# riser-1u-can.net
KiCad netlist of a schematic drawn in EAGLE
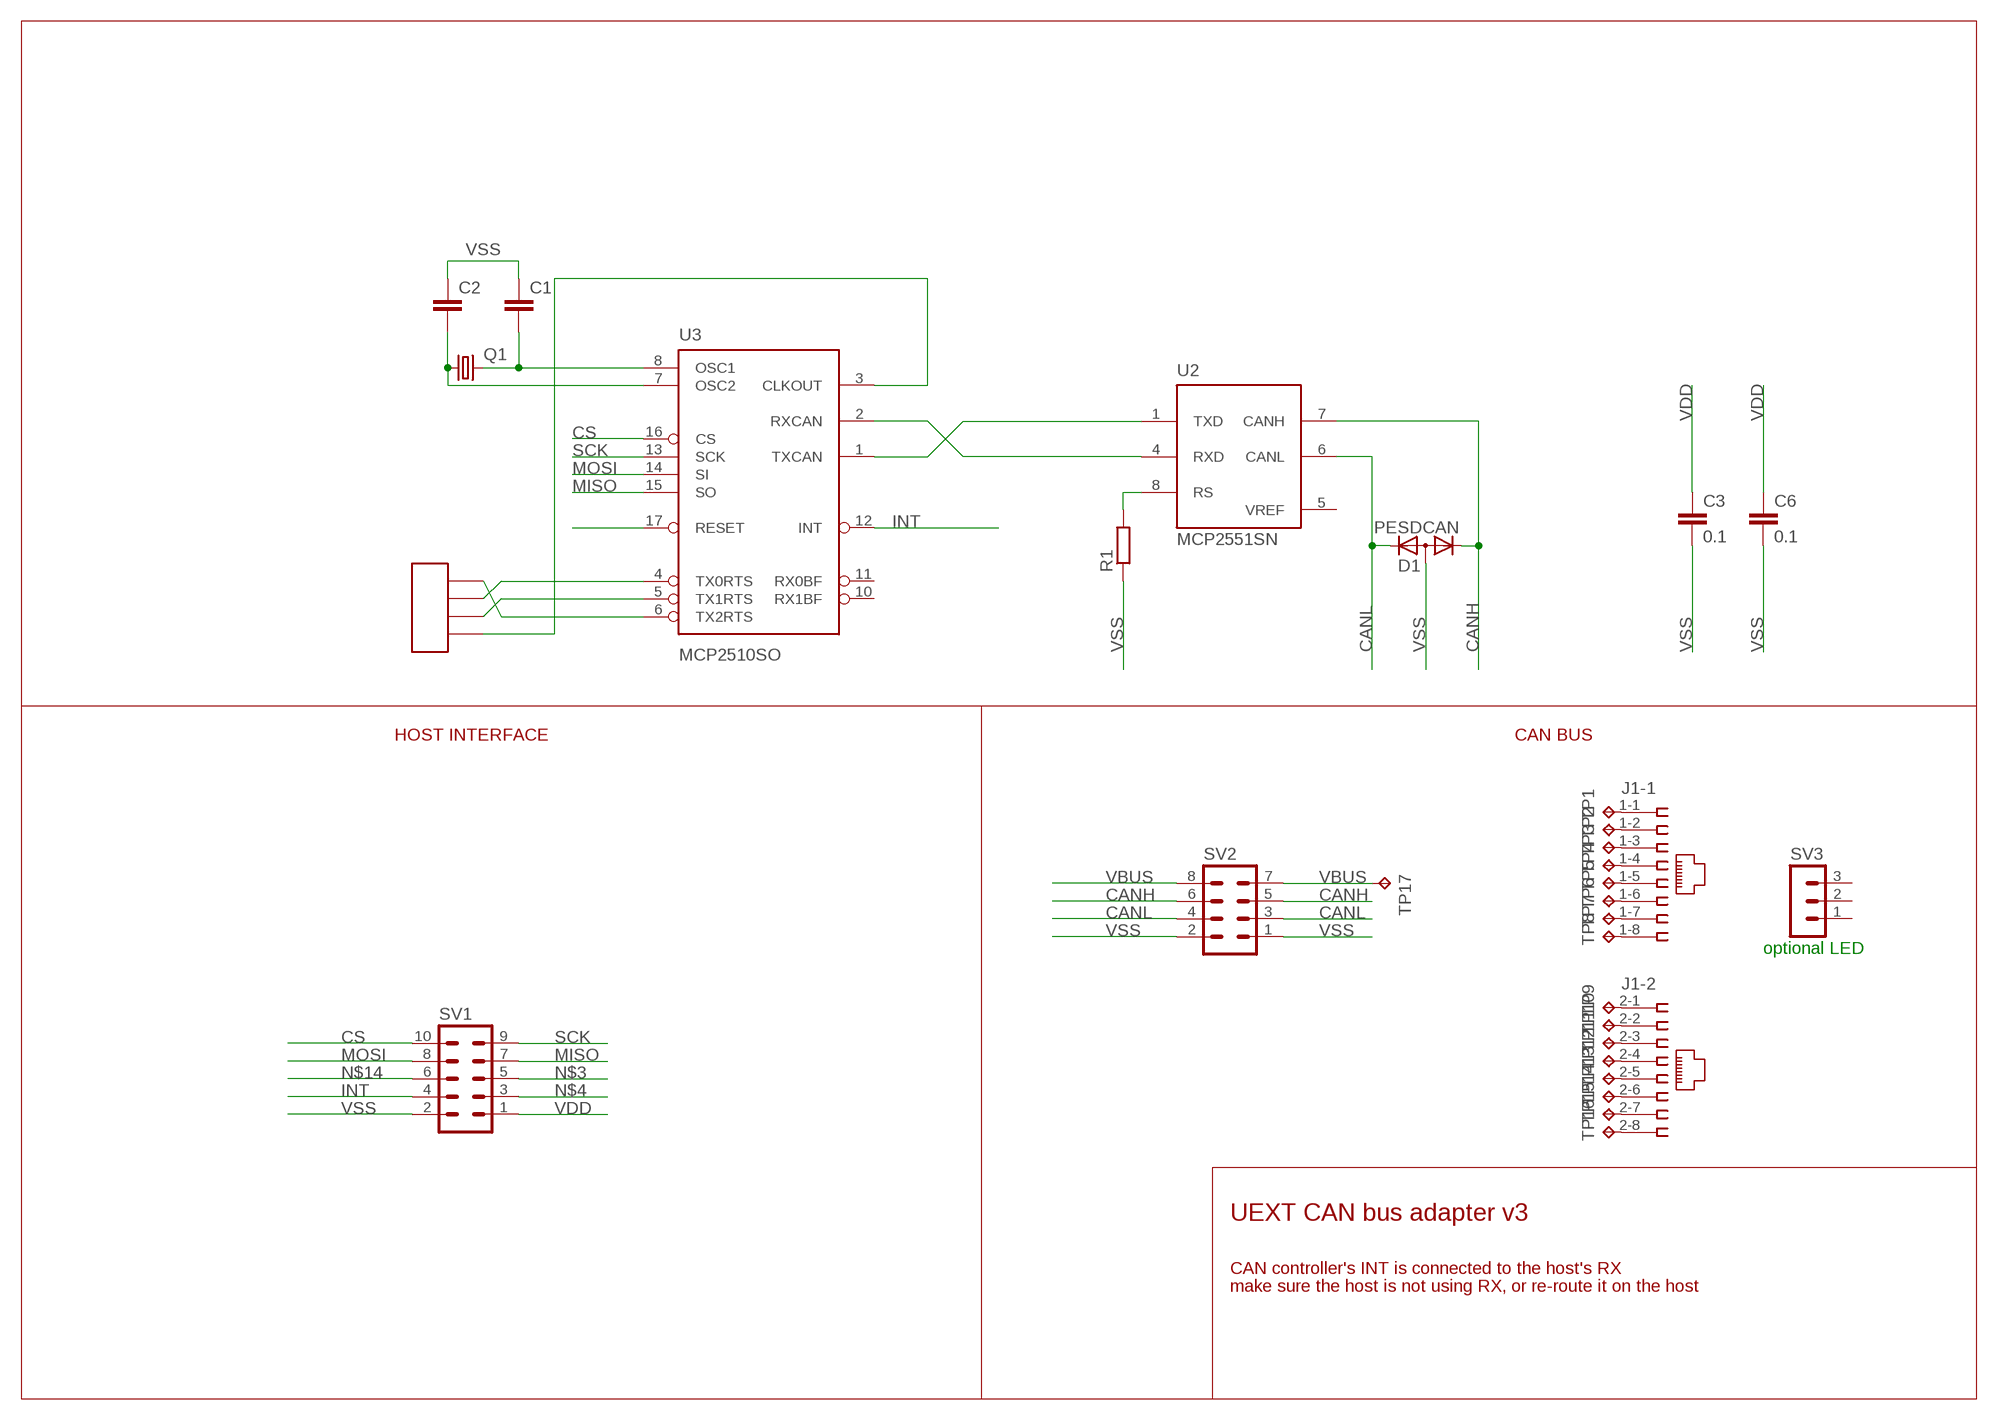
[diagram p0: schematic, sheet 1]

(export (version "E")
  (design (tool "Eeschema 10.0.6"))
  (components
    (comp (ref "C1")
      (value "C-EUC0805")
      (footprint "eagle-import:C0805")
      (libsource (lib "eagle-import") (part "C-EUC0805"))
    )
    (comp (ref "C2")
      (value "C-EUC0805")
      (footprint "eagle-import:C0805")
      (libsource (lib "eagle-import") (part "C-EUC0805"))
    )
    (comp (ref "C3")
      (value "0.1")
      (footprint "eagle-import:C0805")
      (libsource (lib "eagle-import") (part "C-EUC0805"))
    )
    (comp (ref "C6")
      (value "0.1")
      (footprint "eagle-import:C1206")
      (libsource (lib "eagle-import") (part "C-EUC1206"))
    )
    (comp (ref "D1")
      (value "PESDCAN")
      (footprint "eagle-import:SOT23")
      (libsource (lib "eagle-import") (part "DIODE-2CA|ACSOT23"))
    )
    (comp (ref "J1")
      (value "557560-1")
      (footprint "eagle-import:557560-1")
      (libsource (lib "eagle-import") (part "557560-1"))
    )
    (comp (ref "Q1")
      (value "CRYSTALHC49S")
      (footprint "eagle-import:HC49_S")
      (libsource (lib "eagle-import") (part "CRYSTALHC49S"))
    )
    (comp (ref "R1")
      (value "R-EU_R0603")
      (footprint "eagle-import:R0603")
      (libsource (lib "eagle-import") (part "R-EU_R0603"))
    )
    (comp (ref "SV1")
      (value "MA05-2")
      (footprint "eagle-import:MA05-2")
      (libsource (lib "eagle-import") (part "MA05-2"))
    )
    (comp (ref "SV2")
      (value "MA04-2")
      (footprint "eagle-import:MA04-2")
      (libsource (lib "eagle-import") (part "MA04-2"))
    )
    (comp (ref "SV3")
      (value "MA03-1")
      (footprint "eagle-import:MA03-1")
      (libsource (lib "eagle-import") (part "MA03-1"))
    )
    (comp (ref "TP1")
      (value "TPB1,27")
      (footprint "eagle-import:B1,27")
      (libsource (lib "eagle-import") (part "TPB1,27"))
    )
    (comp (ref "TP2")
      (value "TPB1,27")
      (footprint "eagle-import:B1,27")
      (libsource (lib "eagle-import") (part "TPB1,27"))
    )
    (comp (ref "TP3")
      (value "TPB1,27")
      (footprint "eagle-import:B1,27")
      (libsource (lib "eagle-import") (part "TPB1,27"))
    )
    (comp (ref "TP4")
      (value "TPB1,27")
      (footprint "eagle-import:B1,27")
      (libsource (lib "eagle-import") (part "TPB1,27"))
    )
    (comp (ref "TP5")
      (value "TPB1,27")
      (footprint "eagle-import:B1,27")
      (libsource (lib "eagle-import") (part "TPB1,27"))
    )
    (comp (ref "TP6")
      (value "TPB1,27")
      (footprint "eagle-import:B1,27")
      (libsource (lib "eagle-import") (part "TPB1,27"))
    )
    (comp (ref "TP7")
      (value "TPB1,27")
      (footprint "eagle-import:B1,27")
      (libsource (lib "eagle-import") (part "TPB1,27"))
    )
    (comp (ref "TP8")
      (value "TPB1,27")
      (footprint "eagle-import:B1,27")
      (libsource (lib "eagle-import") (part "TPB1,27"))
    )
    (comp (ref "TP9")
      (value "TPB1,27")
      (footprint "eagle-import:B1,27")
      (libsource (lib "eagle-import") (part "TPB1,27"))
    )
    (comp (ref "TP10")
      (value "TPB1,27")
      (footprint "eagle-import:B1,27")
      (libsource (lib "eagle-import") (part "TPB1,27"))
    )
    (comp (ref "TP11")
      (value "TPB1,27")
      (footprint "eagle-import:B1,27")
      (libsource (lib "eagle-import") (part "TPB1,27"))
    )
    (comp (ref "TP12")
      (value "TPB1,27")
      (footprint "eagle-import:B1,27")
      (libsource (lib "eagle-import") (part "TPB1,27"))
    )
    (comp (ref "TP13")
      (value "TPB1,27")
      (footprint "eagle-import:B1,27")
      (libsource (lib "eagle-import") (part "TPB1,27"))
    )
    (comp (ref "TP14")
      (value "TPB1,27")
      (footprint "eagle-import:B1,27")
      (libsource (lib "eagle-import") (part "TPB1,27"))
    )
    (comp (ref "TP15")
      (value "TPB1,27")
      (footprint "eagle-import:B1,27")
      (libsource (lib "eagle-import") (part "TPB1,27"))
    )
    (comp (ref "TP16")
      (value "TPB1,27")
      (footprint "eagle-import:B1,27")
      (libsource (lib "eagle-import") (part "TPB1,27"))
    )
    (comp (ref "TP17")
      (value "TPB1,27")
      (footprint "eagle-import:B1,27")
      (libsource (lib "eagle-import") (part "TPB1,27"))
    )
    (comp (ref "U$2")
      (value "PIN_HEADER_2X2")
      (footprint "eagle-import:PIN_HEADER_2X2")
      (libsource (lib "eagle-import") (part "PIN_HEADER_2X2"))
    )
    (comp (ref "U2")
      (value "MCP2551SN")
      (footprint "eagle-import:SO-08")
      (libsource (lib "eagle-import") (part "MCP2551SN"))
    )
    (comp (ref "U3")
      (value "MCP2510SO")
      (footprint "eagle-import:SO-18W")
      (libsource (lib "eagle-import") (part "MCP2510SO"))
    )
  )
  (nets
    (net (code "1") (name "/CANH") (class "Default")
      (node (ref "D1") (pin "1") (pinfunction "K1_1") (pintype "passive"))
      (node (ref "SV2") (pin "5") (pinfunction "5_5") (pintype "passive"))
      (node (ref "SV2") (pin "6") (pinfunction "6_6") (pintype "passive"))
      (node (ref "U2") (pin "7") (pinfunction "CANH_7") (pintype "bidirectional"))
    )
    (net (code "2") (name "/CANL") (class "Default")
      (node (ref "D1") (pin "2") (pinfunction "K2_2") (pintype "passive"))
      (node (ref "SV2") (pin "3") (pinfunction "3_3") (pintype "passive"))
      (node (ref "SV2") (pin "4") (pinfunction "4_4") (pintype "passive"))
      (node (ref "U2") (pin "6") (pinfunction "CANL_6") (pintype "bidirectional"))
    )
    (net (code "3") (name "/CS") (class "Default")
      (node (ref "SV1") (pin "10") (pinfunction "10_10") (pintype "passive"))
      (node (ref "U3") (pin "16") (pinfunction "CS_16") (pintype "input"))
    )
    (net (code "4") (name "/INT") (class "Default")
      (node (ref "SV1") (pin "4") (pinfunction "4_4") (pintype "passive"))
      (node (ref "U3") (pin "12") (pinfunction "INT_12") (pintype "output"))
    )
    (net (code "5") (name "/MISO") (class "Default")
      (node (ref "SV1") (pin "7") (pinfunction "7_7") (pintype "passive"))
      (node (ref "U3") (pin "15") (pinfunction "SO_15") (pintype "output"))
    )
    (net (code "6") (name "/MOSI") (class "Default")
      (node (ref "SV1") (pin "8") (pinfunction "8_8") (pintype "passive"))
      (node (ref "U3") (pin "14") (pinfunction "SI_14") (pintype "input"))
    )
    (net (code "7") (name "/N$3") (class "Default")
      (node (ref "SV1") (pin "5") (pinfunction "5_5") (pintype "passive"))
    )
    (net (code "8") (name "/N$4") (class "Default")
      (node (ref "SV1") (pin "3") (pinfunction "3_3") (pintype "passive"))
    )
    (net (code "9") (name "/N$14") (class "Default")
      (node (ref "SV1") (pin "6") (pinfunction "6_6") (pintype "passive"))
    )
    (net (code "10") (name "/SCK") (class "Default")
      (node (ref "SV1") (pin "9") (pinfunction "9_9") (pintype "passive"))
      (node (ref "U3") (pin "13") (pinfunction "SCK_13") (pintype "input"))
    )
    (net (code "11") (name "/VBUS") (class "Default")
      (node (ref "SV2") (pin "7") (pinfunction "7_7") (pintype "passive"))
      (node (ref "SV2") (pin "8") (pinfunction "8_8") (pintype "passive"))
      (node (ref "TP17") (pin "TP") (pinfunction "TP_TP") (pintype "input"))
    )
    (net (code "12") (name "/VDD") (class "Default")
      (node (ref "C3") (pin "1") (pinfunction "1_1") (pintype "passive"))
      (node (ref "C6") (pin "1") (pinfunction "1_1") (pintype "passive"))
      (node (ref "SV1") (pin "1") (pinfunction "1_1") (pintype "passive"))
    )
    (net (code "13") (name "/VREF") (class "Default")
      (node (ref "U2") (pin "5") (pinfunction "VREF_5") (pintype "power_in"))
    )
    (net (code "14") (name "/VSS") (class "Default")
      (node (ref "C1") (pin "1") (pinfunction "1_1") (pintype "passive"))
      (node (ref "C2") (pin "1") (pinfunction "1_1") (pintype "passive"))
      (node (ref "C3") (pin "2") (pinfunction "2_2") (pintype "passive"))
      (node (ref "C6") (pin "2") (pinfunction "2_2") (pintype "passive"))
      (node (ref "D1") (pin "3") (pinfunction "A_3") (pintype "passive"))
      (node (ref "R1") (pin "1") (pinfunction "1_1") (pintype "passive"))
      (node (ref "SV1") (pin "2") (pinfunction "2_2") (pintype "passive"))
      (node (ref "SV2") (pin "1") (pinfunction "1_1") (pintype "passive"))
      (node (ref "SV2") (pin "2") (pinfunction "2_2") (pintype "passive"))
    )
    (net (code "15") (name "Net-(J1A-1)") (class "Default")
      (node (ref "J1") (pin "1-1") (pinfunction "1_1-1") (pintype "passive"))
      (node (ref "TP1") (pin "TP") (pinfunction "TP_TP") (pintype "input"))
    )
    (net (code "16") (name "Net-(J1A-2)") (class "Default")
      (node (ref "J1") (pin "1-2") (pinfunction "2_1-2") (pintype "passive"))
      (node (ref "TP2") (pin "TP") (pinfunction "TP_TP") (pintype "input"))
    )
    (net (code "17") (name "Net-(J1A-3)") (class "Default")
      (node (ref "J1") (pin "1-3") (pinfunction "3_1-3") (pintype "passive"))
      (node (ref "TP3") (pin "TP") (pinfunction "TP_TP") (pintype "input"))
    )
    (net (code "18") (name "Net-(J1A-4)") (class "Default")
      (node (ref "J1") (pin "1-4") (pinfunction "4_1-4") (pintype "passive"))
      (node (ref "TP4") (pin "TP") (pinfunction "TP_TP") (pintype "input"))
    )
    (net (code "19") (name "Net-(J1A-5)") (class "Default")
      (node (ref "J1") (pin "1-5") (pinfunction "5_1-5") (pintype "passive"))
      (node (ref "TP5") (pin "TP") (pinfunction "TP_TP") (pintype "input"))
    )
    (net (code "20") (name "Net-(J1A-6)") (class "Default")
      (node (ref "J1") (pin "1-6") (pinfunction "6_1-6") (pintype "passive"))
      (node (ref "TP6") (pin "TP") (pinfunction "TP_TP") (pintype "input"))
    )
    (net (code "21") (name "Net-(J1A-7)") (class "Default")
      (node (ref "J1") (pin "1-7") (pinfunction "7_1-7") (pintype "passive"))
      (node (ref "TP7") (pin "TP") (pinfunction "TP_TP") (pintype "input"))
    )
    (net (code "22") (name "Net-(J1A-8)") (class "Default")
      (node (ref "J1") (pin "1-8") (pinfunction "8_1-8") (pintype "passive"))
      (node (ref "TP8") (pin "TP") (pinfunction "TP_TP") (pintype "input"))
    )
    (net (code "23") (name "Net-(J1B-1)") (class "Default")
      (node (ref "J1") (pin "2-1") (pinfunction "1_2-1") (pintype "passive"))
      (node (ref "TP9") (pin "TP") (pinfunction "TP_TP") (pintype "input"))
    )
    (net (code "24") (name "Net-(J1B-2)") (class "Default")
      (node (ref "J1") (pin "2-2") (pinfunction "2_2-2") (pintype "passive"))
      (node (ref "TP10") (pin "TP") (pinfunction "TP_TP") (pintype "input"))
    )
    (net (code "25") (name "Net-(J1B-3)") (class "Default")
      (node (ref "J1") (pin "2-3") (pinfunction "3_2-3") (pintype "passive"))
      (node (ref "TP11") (pin "TP") (pinfunction "TP_TP") (pintype "input"))
    )
    (net (code "26") (name "Net-(J1B-4)") (class "Default")
      (node (ref "J1") (pin "2-4") (pinfunction "4_2-4") (pintype "passive"))
      (node (ref "TP12") (pin "TP") (pinfunction "TP_TP") (pintype "input"))
    )
    (net (code "27") (name "Net-(J1B-5)") (class "Default")
      (node (ref "J1") (pin "2-5") (pinfunction "5_2-5") (pintype "passive"))
      (node (ref "TP13") (pin "TP") (pinfunction "TP_TP") (pintype "input"))
    )
    (net (code "28") (name "Net-(J1B-6)") (class "Default")
      (node (ref "J1") (pin "2-6") (pinfunction "6_2-6") (pintype "passive"))
      (node (ref "TP14") (pin "TP") (pinfunction "TP_TP") (pintype "input"))
    )
    (net (code "29") (name "Net-(J1B-7)") (class "Default")
      (node (ref "J1") (pin "2-7") (pinfunction "7_2-7") (pintype "passive"))
      (node (ref "TP15") (pin "TP") (pinfunction "TP_TP") (pintype "input"))
    )
    (net (code "30") (name "Net-(J1B-8)") (class "Default")
      (node (ref "J1") (pin "2-8") (pinfunction "8_2-8") (pintype "passive"))
      (node (ref "TP16") (pin "TP") (pinfunction "TP_TP") (pintype "input"))
    )
    (net (code "31") (name "Net-(U2A-RS)") (class "Default")
      (node (ref "R1") (pin "2") (pinfunction "2_2") (pintype "passive"))
      (node (ref "U2") (pin "8") (pinfunction "RS_8") (pintype "input"))
    )
    (net (code "32") (name "Net-(U2A-RXD)") (class "Default")
      (node (ref "U2") (pin "4") (pinfunction "RXD_4") (pintype "output"))
      (node (ref "U3") (pin "2") (pinfunction "RXCAN_2") (pintype "input"))
    )
    (net (code "33") (name "Net-(U2A-TXD)") (class "Default")
      (node (ref "U2") (pin "1") (pinfunction "TXD_1") (pintype "input"))
      (node (ref "U3") (pin "1") (pinfunction "TXCAN_1") (pintype "output"))
    )
    (net (code "34") (name "Net-(U3A-CLKOUT)") (class "Default")
      (node (ref "U$2") (pin "P$4") (pinfunction "P$4_P$4") (pintype "bidirectional"))
      (node (ref "U3") (pin "3") (pinfunction "CLKOUT_3") (pintype "output"))
    )
    (net (code "35") (name "Net-(U3A-OSC1)") (class "Default")
      (node (ref "C1") (pin "2") (pinfunction "2_2") (pintype "passive"))
      (node (ref "Q1") (pin "2") (pinfunction "2_2") (pintype "passive"))
      (node (ref "U3") (pin "8") (pinfunction "OSC1_8") (pintype "input"))
    )
    (net (code "36") (name "Net-(U3A-OSC2)") (class "Default")
      (node (ref "C2") (pin "2") (pinfunction "2_2") (pintype "passive"))
      (node (ref "Q1") (pin "1") (pinfunction "1_1") (pintype "passive"))
      (node (ref "U3") (pin "7") (pinfunction "OSC2_7") (pintype "output"))
    )
    (net (code "37") (name "Net-(U3A-TX0RTS)") (class "Default")
      (node (ref "U$2") (pin "P$2") (pinfunction "P$2_P$2") (pintype "bidirectional"))
      (node (ref "U3") (pin "4") (pinfunction "TX0RTS_4") (pintype "input"))
    )
    (net (code "38") (name "Net-(U3A-TX1RTS)") (class "Default")
      (node (ref "U$2") (pin "P$3") (pinfunction "P$3_P$3") (pintype "bidirectional"))
      (node (ref "U3") (pin "5") (pinfunction "TX1RTS_5") (pintype "input"))
    )
    (net (code "39") (name "Net-(U3A-TX2RTS)") (class "Default")
      (node (ref "U$2") (pin "P$1") (pinfunction "P$1_P$1") (pintype "bidirectional"))
      (node (ref "U3") (pin "6") (pinfunction "TX2RTS_6") (pintype "input"))
    )
    (net (code "40") (name "unconnected-(SV3-Pad1)") (class "Default")
      (node (ref "SV3") (pin "1") (pinfunction "1_1") (pintype "passive"))
    )
    (net (code "41") (name "unconnected-(SV3-Pad2)") (class "Default")
      (node (ref "SV3") (pin "2") (pinfunction "2_2") (pintype "passive"))
    )
    (net (code "42") (name "unconnected-(SV3-Pad3)") (class "Default")
      (node (ref "SV3") (pin "3") (pinfunction "3_3") (pintype "passive"))
    )
    (net (code "43") (name "unconnected-(U3A-RESET-Pad17)") (class "Default")
      (node (ref "U3") (pin "17") (pinfunction "RESET_17") (pintype "input"))
    )
    (net (code "44") (name "unconnected-(U3A-RX0BF-Pad11)") (class "Default")
      (node (ref "U3") (pin "11") (pinfunction "RX0BF_11") (pintype "output"))
    )
    (net (code "45") (name "unconnected-(U3A-RX1BF-Pad10)") (class "Default")
      (node (ref "U3") (pin "10") (pinfunction "RX1BF_10") (pintype "output"))
    )
  )
)
